# Main-v2_0.net
KiCad netlist of a schematic drawn in EAGLE
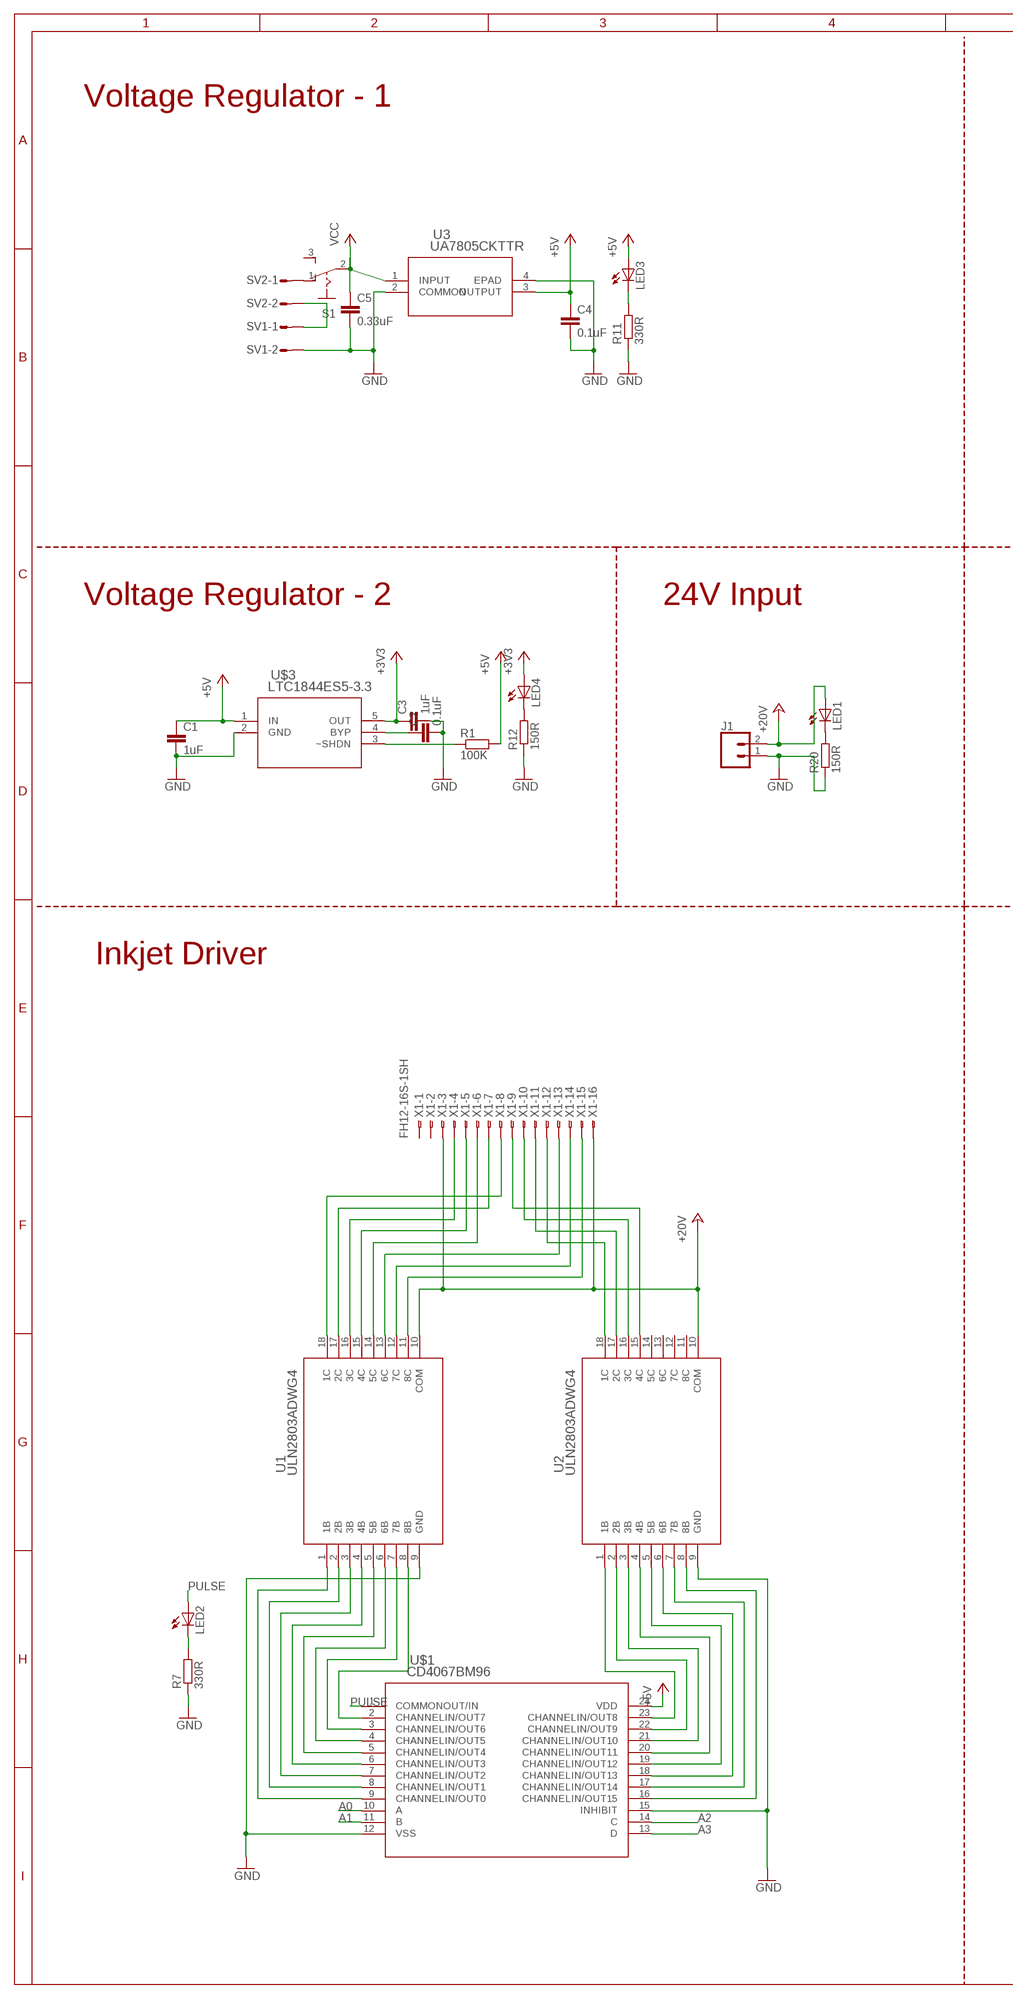
[diagram p0: schematic, sheet 1, part 1 of 2]
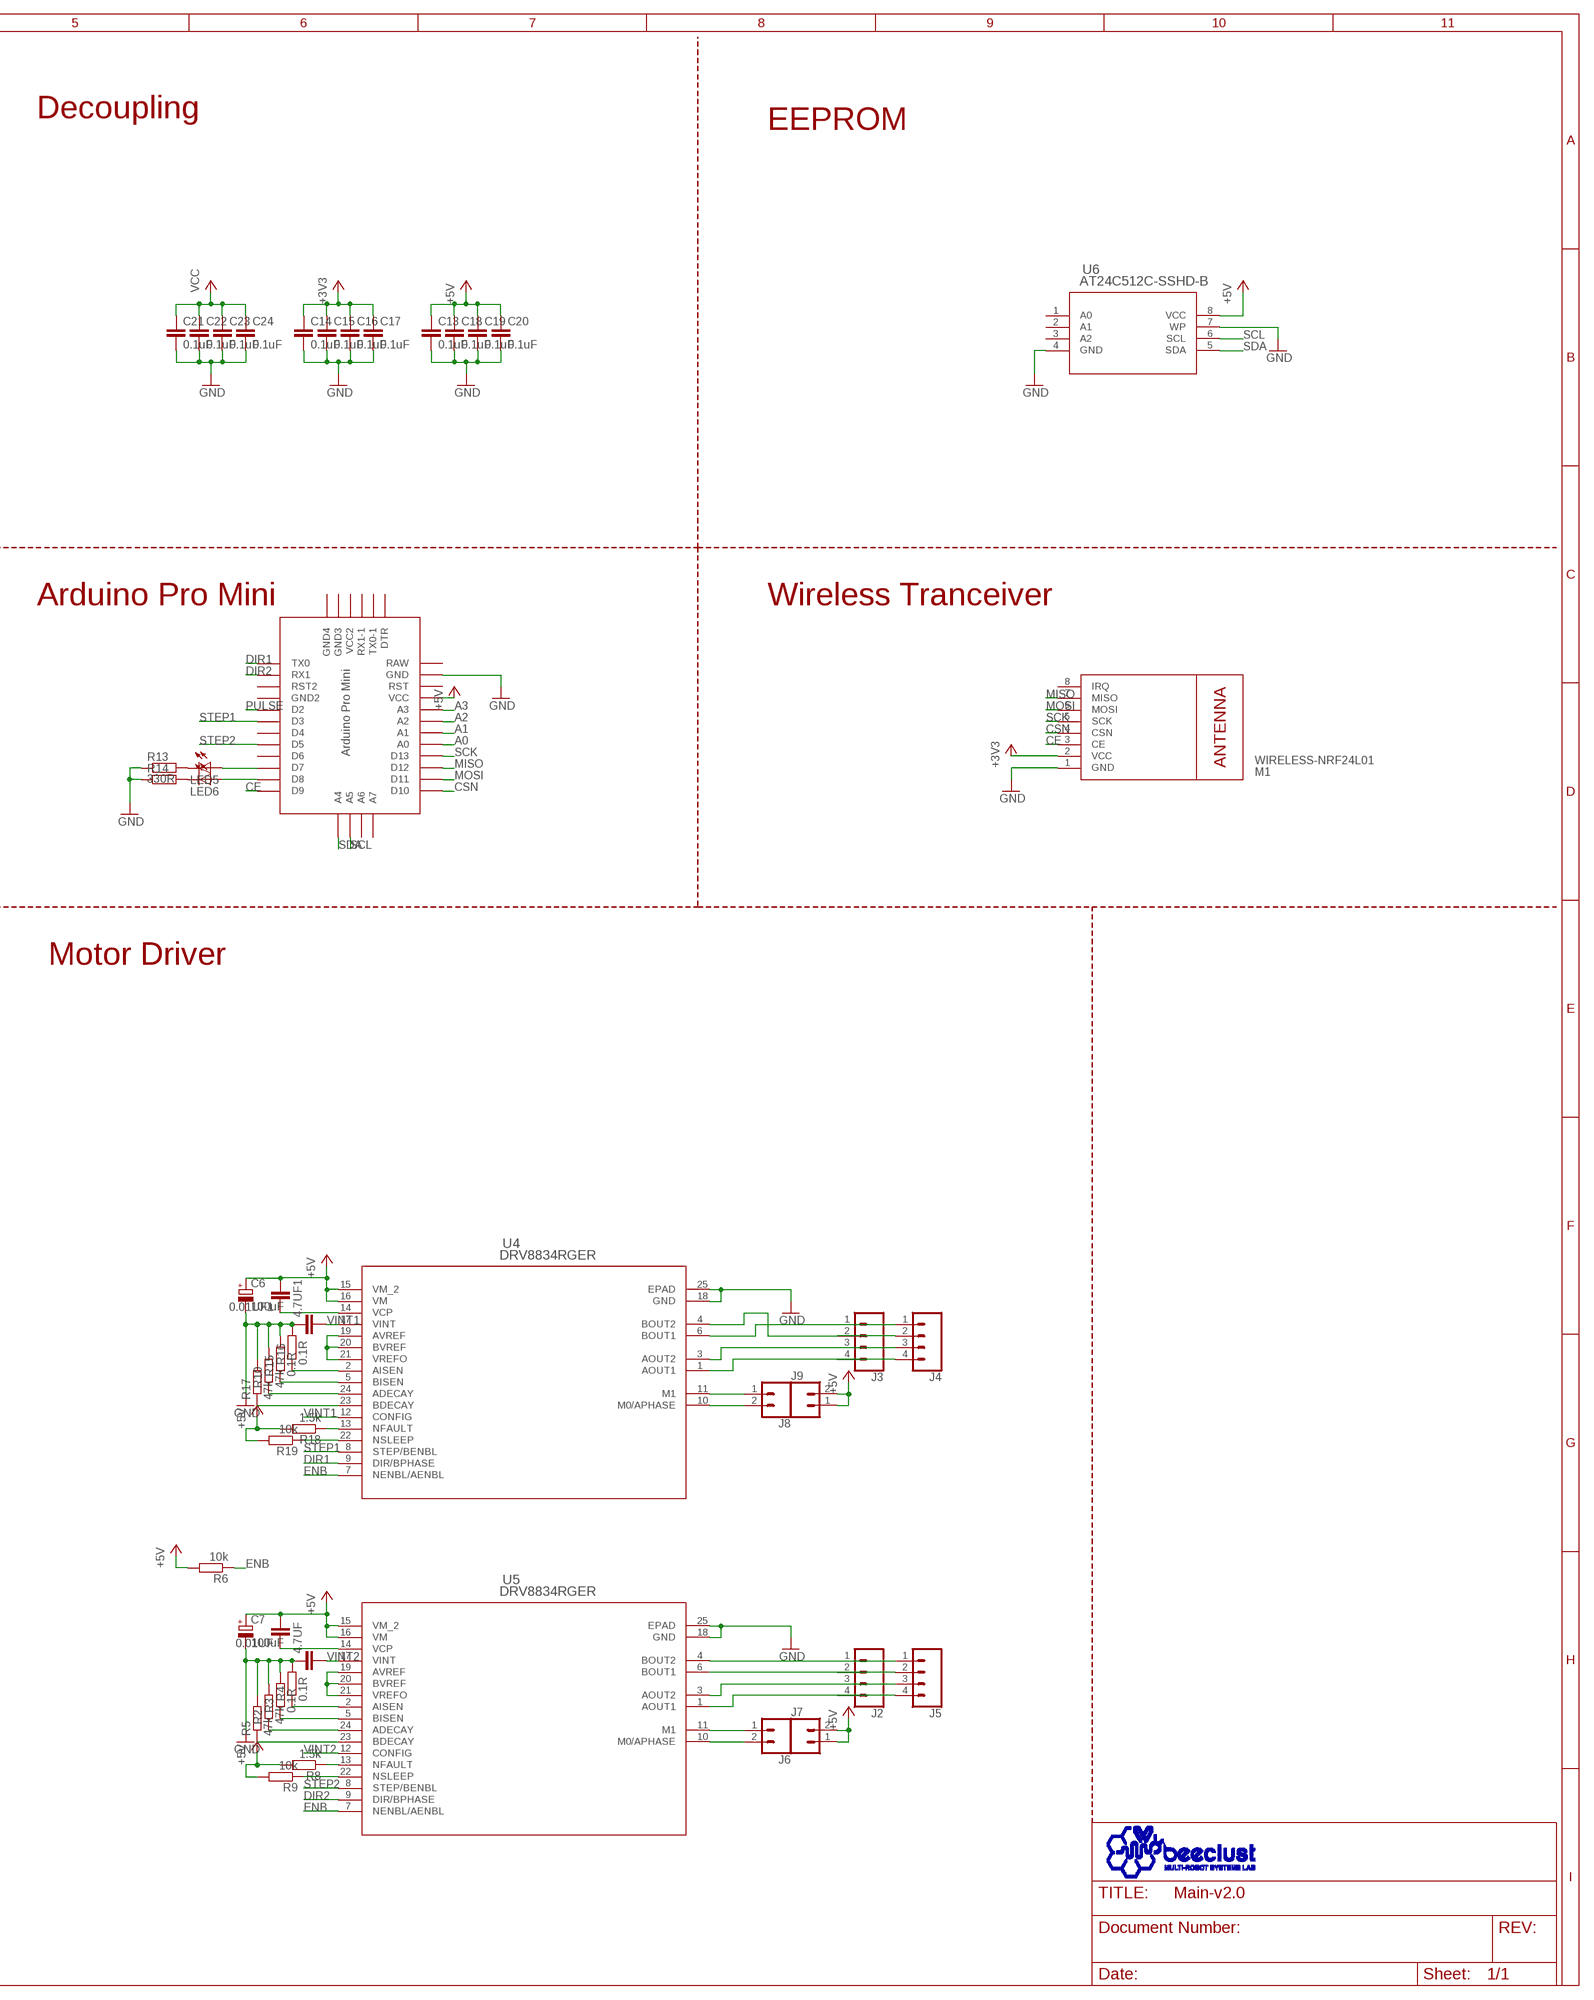
[diagram p1: schematic, sheet 1, part 2 of 2]

(export (version "E")
  (design (tool "Eeschema 10.0.6"))
  (components
    (comp (ref "0.01UF")
      (value "C-EUC0603K")
      (footprint "eagle-import:C0603K")
      (libsource (lib "eagle-import") (part "resistor_348_C-EUC0603K"))
    )
    (comp (ref "0.01UF1")
      (value "C-EUC0603K")
      (footprint "eagle-import:C0603K")
      (libsource (lib "eagle-import") (part "resistor_348_C-EUC0603K"))
    )
    (comp (ref "4.7UF")
      (value "C-EUC0603K")
      (footprint "eagle-import:C0603K")
      (libsource (lib "eagle-import") (part "resistor_348_C-EUC0603K"))
    )
    (comp (ref "4.7UF1")
      (value "C-EUC0603K")
      (footprint "eagle-import:C0603K")
      (libsource (lib "eagle-import") (part "resistor_348_C-EUC0603K"))
    )
    (comp (ref "C1")
      (value "1uF")
      (footprint "eagle-import:C0603")
      (libsource (lib "eagle-import") (part "C-EUC0603"))
    )
    (comp (ref "C2")
      (value "0.1uF")
      (footprint "eagle-import:C0603")
      (libsource (lib "eagle-import") (part "C-EUC0603"))
    )
    (comp (ref "C3")
      (value "1uF")
      (footprint "eagle-import:C0603")
      (libsource (lib "eagle-import") (part "C-EUC0603"))
    )
    (comp (ref "C4")
      (value "0.1uF")
      (footprint "eagle-import:C0603")
      (libsource (lib "eagle-import") (part "C-EUC0603"))
    )
    (comp (ref "C5")
      (value "0.33uF")
      (footprint "eagle-import:C0603")
      (libsource (lib "eagle-import") (part "C-EUC0603"))
    )
    (comp (ref "C6")
      (value "100uF")
      (footprint "eagle-import:E5-5")
      (libsource (lib "eagle-import") (part "CPOL-EUE5-5"))
    )
    (comp (ref "C7")
      (value "100uF")
      (footprint "eagle-import:E5-5")
      (libsource (lib "eagle-import") (part "CPOL-EUE5-5"))
    )
    (comp (ref "C13")
      (value "0.1uF")
      (footprint "eagle-import:C0603")
      (libsource (lib "eagle-import") (part "C-EUC0603"))
    )
    (comp (ref "C14")
      (value "0.1uF")
      (footprint "eagle-import:C0603")
      (libsource (lib "eagle-import") (part "C-EUC0603"))
    )
    (comp (ref "C15")
      (value "0.1uF")
      (footprint "eagle-import:C0603")
      (libsource (lib "eagle-import") (part "C-EUC0603"))
    )
    (comp (ref "C16")
      (value "0.1uF")
      (footprint "eagle-import:C0603")
      (libsource (lib "eagle-import") (part "C-EUC0603"))
    )
    (comp (ref "C17")
      (value "0.1uF")
      (footprint "eagle-import:C0603")
      (libsource (lib "eagle-import") (part "C-EUC0603"))
    )
    (comp (ref "C18")
      (value "0.1uF")
      (footprint "eagle-import:C0603")
      (libsource (lib "eagle-import") (part "C-EUC0603"))
    )
    (comp (ref "C19")
      (value "0.1uF")
      (footprint "eagle-import:C0603")
      (libsource (lib "eagle-import") (part "C-EUC0603"))
    )
    (comp (ref "C20")
      (value "0.1uF")
      (footprint "eagle-import:C0603")
      (libsource (lib "eagle-import") (part "C-EUC0603"))
    )
    (comp (ref "C21")
      (value "0.1uF")
      (footprint "eagle-import:C0603")
      (libsource (lib "eagle-import") (part "C-EUC0603"))
    )
    (comp (ref "C22")
      (value "0.1uF")
      (footprint "eagle-import:C0603")
      (libsource (lib "eagle-import") (part "C-EUC0603"))
    )
    (comp (ref "C23")
      (value "0.1uF")
      (footprint "eagle-import:C0603")
      (libsource (lib "eagle-import") (part "C-EUC0603"))
    )
    (comp (ref "C24")
      (value "0.1uF")
      (footprint "eagle-import:C0603")
      (libsource (lib "eagle-import") (part "C-EUC0603"))
    )
    (comp (ref "J1")
      (value "CONN_02")
      (footprint "eagle-import:1X02")
      (libsource (lib "eagle-import") (part "CONN_02"))
    )
    (comp (ref "J2")
      (value "CONN_04")
      (footprint "eagle-import:1X04")
      (libsource (lib "eagle-import") (part "CONN_04"))
    )
    (comp (ref "J3")
      (value "CONN_04")
      (footprint "eagle-import:1X04")
      (libsource (lib "eagle-import") (part "CONN_04"))
    )
    (comp (ref "J4")
      (value "CONN_04")
      (footprint "eagle-import:1X04")
      (libsource (lib "eagle-import") (part "CONN_04"))
    )
    (comp (ref "J5")
      (value "CONN_04")
      (footprint "eagle-import:1X04")
      (libsource (lib "eagle-import") (part "CONN_04"))
    )
    (comp (ref "J6")
      (value "CONN_02")
      (footprint "eagle-import:1X02")
      (libsource (lib "eagle-import") (part "CONN_02"))
    )
    (comp (ref "J7")
      (value "CONN_02")
      (footprint "eagle-import:1X02")
      (libsource (lib "eagle-import") (part "CONN_02"))
    )
    (comp (ref "J8")
      (value "CONN_02")
      (footprint "eagle-import:1X02")
      (libsource (lib "eagle-import") (part "CONN_02"))
    )
    (comp (ref "J9")
      (value "CONN_02")
      (footprint "eagle-import:1X02")
      (libsource (lib "eagle-import") (part "CONN_02"))
    )
    (comp (ref "LED1")
      (value "LEDSML0603")
      (footprint "eagle-import:SML0603")
      (libsource (lib "eagle-import") (part "LEDSML0603"))
    )
    (comp (ref "LED2")
      (value "LEDSML0603")
      (footprint "eagle-import:SML0603")
      (libsource (lib "eagle-import") (part "LEDSML0603"))
    )
    (comp (ref "LED3")
      (value "LEDSML0603")
      (footprint "eagle-import:SML0603")
      (libsource (lib "eagle-import") (part "LEDSML0603"))
    )
    (comp (ref "LED4")
      (value "LEDSML0603")
      (footprint "eagle-import:SML0603")
      (libsource (lib "eagle-import") (part "LEDSML0603"))
    )
    (comp (ref "LED5")
      (value "LEDSML0603")
      (footprint "eagle-import:SML0603")
      (libsource (lib "eagle-import") (part "LEDSML0603"))
    )
    (comp (ref "LED6")
      (value "LEDSML0603")
      (footprint "eagle-import:SML0603")
      (libsource (lib "eagle-import") (part "LEDSML0603"))
    )
    (comp (ref "M1")
      (value "WIRELESS-NRF24L01")
      (footprint "eagle-import:WIRELESS-NRF24L01")
      (libsource (lib "eagle-import") (part "WIRELESS-NRF24L01"))
    )
    (comp (ref "R1")
      (value "100K")
      (footprint "eagle-import:R0603")
      (libsource (lib "eagle-import") (part "R-EU_R0603"))
    )
    (comp (ref "R2")
      (value "47k")
      (footprint "eagle-import:R0402")
      (libsource (lib "eagle-import") (part "resistor_348_R-EU_R0402"))
    )
    (comp (ref "R3")
      (value "0.1R")
      (footprint "eagle-import:R0402")
      (libsource (lib "eagle-import") (part "resistor_348_R-EU_R0402"))
    )
    (comp (ref "R4")
      (value "0.1R")
      (footprint "eagle-import:R0402")
      (libsource (lib "eagle-import") (part "resistor_348_R-EU_R0402"))
    )
    (comp (ref "R5")
      (value "47k")
      (footprint "eagle-import:R0402")
      (libsource (lib "eagle-import") (part "resistor_348_R-EU_R0402"))
    )
    (comp (ref "R6")
      (value "10k")
      (footprint "eagle-import:R0402")
      (libsource (lib "eagle-import") (part "resistor_348_R-EU_R0402"))
    )
    (comp (ref "R7")
      (value "330R")
      (footprint "eagle-import:R0603")
      (libsource (lib "eagle-import") (part "R-EU_R0603"))
    )
    (comp (ref "R8")
      (value "1.5k")
      (footprint "eagle-import:R0402")
      (libsource (lib "eagle-import") (part "resistor_348_R-EU_R0402"))
    )
    (comp (ref "R9")
      (value "10k")
      (footprint "eagle-import:R0402")
      (libsource (lib "eagle-import") (part "resistor_348_R-EU_R0402"))
    )
    (comp (ref "R10")
      (value "47k")
      (footprint "eagle-import:R0402")
      (libsource (lib "eagle-import") (part "resistor_348_R-EU_R0402"))
    )
    (comp (ref "R11")
      (value "330R")
      (footprint "eagle-import:R0603")
      (libsource (lib "eagle-import") (part "R-EU_R0603"))
    )
    (comp (ref "R12")
      (value "150R")
      (footprint "eagle-import:R0603")
      (libsource (lib "eagle-import") (part "R-EU_R0603"))
    )
    (comp (ref "R13")
      (value "330R")
      (footprint "eagle-import:R0603")
      (libsource (lib "eagle-import") (part "R-EU_R0603"))
    )
    (comp (ref "R14")
      (value "R-EU_R0603")
      (footprint "eagle-import:R0603")
      (libsource (lib "eagle-import") (part "R-EU_R0603"))
    )
    (comp (ref "R15")
      (value "0.1R")
      (footprint "eagle-import:R0402")
      (libsource (lib "eagle-import") (part "resistor_348_R-EU_R0402"))
    )
    (comp (ref "R16")
      (value "0.1R")
      (footprint "eagle-import:R0402")
      (libsource (lib "eagle-import") (part "resistor_348_R-EU_R0402"))
    )
    (comp (ref "R17")
      (value "47k")
      (footprint "eagle-import:R0402")
      (libsource (lib "eagle-import") (part "resistor_348_R-EU_R0402"))
    )
    (comp (ref "R18")
      (value "1.5k")
      (footprint "eagle-import:R0402")
      (libsource (lib "eagle-import") (part "resistor_348_R-EU_R0402"))
    )
    (comp (ref "R19")
      (value "10k")
      (footprint "eagle-import:R0402")
      (libsource (lib "eagle-import") (part "resistor_348_R-EU_R0402"))
    )
    (comp (ref "R20")
      (value "150R")
      (footprint "eagle-import:R0603")
      (libsource (lib "eagle-import") (part "R-EU_R0603"))
    )
    (comp (ref "S1")
      (value "255SB")
      (footprint "eagle-import:255SB")
      (libsource (lib "eagle-import") (part "255SB"))
    )
    (comp (ref "SV1")
      (value "L02P")
      (footprint "eagle-import:L02P")
      (libsource (lib "eagle-import") (part "L02P"))
    )
    (comp (ref "SV2")
      (value "L02P")
      (footprint "eagle-import:L02P")
      (libsource (lib "eagle-import") (part "L02P"))
    )
    (comp (ref "U$1")
      (value "CD4067BM96")
      (footprint "eagle-import:DW24")
      (fields (field (name "MANUFACTURER_PART_NUMBER") "CD4067B_DW_24"))
      (libsource (lib "eagle-import") (part "CD4067BM96"))
    )
    (comp (ref "U$2")
      (value "PRO-MINI")
      (footprint "eagle-import:PRO-MINI")
      (libsource (lib "eagle-import") (part "PRO-MINI"))
    )
    (comp (ref "U$3")
      (value "LTC1844ES5-3.3")
      (footprint "eagle-import:TSOT-23_S5")
      (libsource (lib "eagle-import") (part "LTC1844ES5-3.3"))
    )
    (comp (ref "U$5")
      (value "BEECLUST-LOGO")
      (footprint "eagle-import:LOGO")
      (libsource (lib "eagle-import") (part "BEECLUST-LOGO"))
    )
    (comp (ref "U1")
      (value "ULN2803ADWG4")
      (footprint "eagle-import:DW18")
      (libsource (lib "eagle-import") (part "ULN2803ADWG4"))
    )
    (comp (ref "U2")
      (value "ULN2803ADWG4")
      (footprint "eagle-import:DW18")
      (libsource (lib "eagle-import") (part "ULN2803ADWG4"))
    )
    (comp (ref "U3")
      (value "UA7805CKTTR")
      (footprint "eagle-import:KTT3_6P22X6P6")
      (libsource (lib "eagle-import") (part "UA7805CKTTR"))
    )
    (comp (ref "U4")
      (value "DRV8834RGER")
      (footprint "eagle-import:RGE24_2P45X2P45")
      (libsource (lib "eagle-import") (part "DRV8834RGER"))
    )
    (comp (ref "U5")
      (value "DRV8834RGER")
      (footprint "eagle-import:RGE24_2P45X2P45")
      (libsource (lib "eagle-import") (part "DRV8834RGER"))
    )
    (comp (ref "U6")
      (value "AT24C512C-SSHD-B")
      (footprint "eagle-import:8S1")
      (fields (field (name "MANUFACTURER_PART_NUMBER") "AT24C512CSSHDB"))
      (libsource (lib "eagle-import") (part "AT24C512C-SSHD-B"))
    )
    (comp (ref "X1")
      (value "FH12-16S-1SH")
      (footprint "eagle-import:FH12-16S-1SH")
      (libsource (lib "eagle-import") (part "FH12-16S-1SH"))
    )
  )
  (nets
    (net (code "1") (name "+3V3") (class "Default")
      (node (ref "C14") (pin "1") (pinfunction "1_1") (pintype "passive"))
      (node (ref "C15") (pin "1") (pinfunction "1_1") (pintype "passive"))
      (node (ref "C16") (pin "1") (pinfunction "1_1") (pintype "passive"))
      (node (ref "C17") (pin "1") (pinfunction "1_1") (pintype "passive"))
      (node (ref "C3") (pin "1") (pinfunction "1_1") (pintype "passive"))
      (node (ref "LED4") (pin "A") (pinfunction "A_A") (pintype "passive"))
      (node (ref "M1") (pin "2") (pinfunction "VCC_2") (pintype "power_in"))
      (node (ref "U$3") (pin "5") (pinfunction "OUT_5") (pintype "passive"))
    )
    (net (code "2") (name "+5V") (class "Default")
      (node (ref "0.01UF") (pin "2") (pinfunction "2_2") (pintype "passive"))
      (node (ref "0.01UF1") (pin "2") (pinfunction "2_2") (pintype "passive"))
      (node (ref "C1") (pin "1") (pinfunction "1_1") (pintype "passive"))
      (node (ref "C13") (pin "1") (pinfunction "1_1") (pintype "passive"))
      (node (ref "C18") (pin "1") (pinfunction "1_1") (pintype "passive"))
      (node (ref "C19") (pin "1") (pinfunction "1_1") (pintype "passive"))
      (node (ref "C20") (pin "1") (pinfunction "1_1") (pintype "passive"))
      (node (ref "C4") (pin "1") (pinfunction "1_1") (pintype "passive"))
      (node (ref "C6") (pin "+") (pinfunction "+_+") (pintype "passive"))
      (node (ref "C7") (pin "+") (pinfunction "+_+") (pintype "passive"))
      (node (ref "J7") (pin "1") (pinfunction "1_1") (pintype "passive"))
      (node (ref "J7") (pin "2") (pinfunction "2_2") (pintype "passive"))
      (node (ref "J9") (pin "1") (pinfunction "1_1") (pintype "passive"))
      (node (ref "J9") (pin "2") (pinfunction "2_2") (pintype "passive"))
      (node (ref "LED3") (pin "A") (pinfunction "A_A") (pintype "passive"))
      (node (ref "R1") (pin "2") (pinfunction "2_2") (pintype "passive"))
      (node (ref "R18") (pin "2") (pinfunction "2_2") (pintype "passive"))
      (node (ref "R19") (pin "2") (pinfunction "2_2") (pintype "passive"))
      (node (ref "R6") (pin "2") (pinfunction "2_2") (pintype "passive"))
      (node (ref "R8") (pin "2") (pinfunction "2_2") (pintype "passive"))
      (node (ref "R9") (pin "2") (pinfunction "2_2") (pintype "passive"))
      (node (ref "U$1") (pin "24") (pinfunction "VDD_24") (pintype "power_in"))
      (node (ref "U$2") (pin "VCC") (pinfunction "VCC_VCC") (pintype "bidirectional"))
      (node (ref "U$3") (pin "1") (pinfunction "IN_1") (pintype "passive"))
      (node (ref "U3") (pin "3") (pinfunction "OUTPUT_3") (pintype "output"))
      (node (ref "U4") (pin "15") (pinfunction "VM_2_15") (pintype "power_in"))
      (node (ref "U4") (pin "16") (pinfunction "VM_16") (pintype "power_in"))
      (node (ref "U5") (pin "15") (pinfunction "VM_2_15") (pintype "power_in"))
      (node (ref "U5") (pin "16") (pinfunction "VM_16") (pintype "power_in"))
      (node (ref "U6") (pin "8") (pinfunction "VCC_8") (pintype "power_in"))
    )
    (net (code "3") (name "+20V") (class "Default")
      (node (ref "J1") (pin "2") (pinfunction "2_2") (pintype "passive"))
      (node (ref "LED1") (pin "A") (pinfunction "A_A") (pintype "passive"))
      (node (ref "U1") (pin "10") (pinfunction "COM_10") (pintype "passive"))
      (node (ref "U2") (pin "10") (pinfunction "COM_10") (pintype "passive"))
      (node (ref "X1") (pin "16") (pinfunction "1_16") (pintype "passive"))
      (node (ref "X1") (pin "3") (pinfunction "1_3") (pintype "passive"))
    )
    (net (code "4") (name "/A0") (class "Default")
      (node (ref "U$1") (pin "10") (pinfunction "A_10") (pintype "passive"))
      (node (ref "U$2") (pin "A0") (pinfunction "A0_A0") (pintype "bidirectional"))
    )
    (net (code "5") (name "/A1") (class "Default")
      (node (ref "U$1") (pin "11") (pinfunction "B_11") (pintype "passive"))
      (node (ref "U$2") (pin "A1") (pinfunction "A1_A1") (pintype "bidirectional"))
    )
    (net (code "6") (name "/A2") (class "Default")
      (node (ref "U$1") (pin "14") (pinfunction "C_14") (pintype "passive"))
      (node (ref "U$2") (pin "A2") (pinfunction "A2_A2") (pintype "bidirectional"))
    )
    (net (code "7") (name "/A3") (class "Default")
      (node (ref "U$1") (pin "13") (pinfunction "D_13") (pintype "passive"))
      (node (ref "U$2") (pin "A3") (pinfunction "A3_A3") (pintype "bidirectional"))
    )
    (net (code "8") (name "/CE") (class "Default")
      (node (ref "M1") (pin "3") (pinfunction "CE_3") (pintype "bidirectional"))
      (node (ref "U$2") (pin "D9") (pinfunction "D9_D9") (pintype "bidirectional"))
    )
    (net (code "9") (name "/CSN") (class "Default")
      (node (ref "M1") (pin "4") (pinfunction "CSN_4") (pintype "bidirectional"))
      (node (ref "U$2") (pin "D10") (pinfunction "D10_D10") (pintype "bidirectional"))
    )
    (net (code "10") (name "/DIR1") (class "Default")
      (node (ref "U$2") (pin "TX0") (pinfunction "TX0_TX0") (pintype "bidirectional"))
      (node (ref "U4") (pin "9") (pinfunction "DIR/BPHASE_9") (pintype "input"))
    )
    (net (code "11") (name "/DIR2") (class "Default")
      (node (ref "U$2") (pin "RX1") (pinfunction "RX1_RX1") (pintype "bidirectional"))
      (node (ref "U5") (pin "9") (pinfunction "DIR/BPHASE_9") (pintype "input"))
    )
    (net (code "12") (name "/ENB") (class "Default")
      (node (ref "R6") (pin "1") (pinfunction "1_1") (pintype "passive"))
      (node (ref "U4") (pin "7") (pinfunction "NENBL/AENBL_7") (pintype "input"))
      (node (ref "U5") (pin "7") (pinfunction "NENBL/AENBL_7") (pintype "input"))
    )
    (net (code "13") (name "/MISO") (class "Default")
      (node (ref "M1") (pin "7") (pinfunction "MISO_7") (pintype "bidirectional"))
      (node (ref "U$2") (pin "D12") (pinfunction "D12_D12") (pintype "bidirectional"))
    )
    (net (code "14") (name "/MOSI") (class "Default")
      (node (ref "M1") (pin "6") (pinfunction "MOSI_6") (pintype "bidirectional"))
      (node (ref "U$2") (pin "D11") (pinfunction "D11_D11") (pintype "bidirectional"))
    )
    (net (code "15") (name "/PULSE") (class "Default")
      (node (ref "LED2") (pin "A") (pinfunction "A_A") (pintype "passive"))
      (node (ref "U$1") (pin "1") (pinfunction "COMMONOUT/IN_1") (pintype "bidirectional"))
      (node (ref "U$2") (pin "D2") (pinfunction "D2_D2") (pintype "bidirectional"))
    )
    (net (code "16") (name "/RAW") (class "Default")
      (node (ref "U$2") (pin "RAW") (pinfunction "RAW_RAW") (pintype "power_in"))
    )
    (net (code "17") (name "/SCK") (class "Default")
      (node (ref "M1") (pin "5") (pinfunction "SCK_5") (pintype "bidirectional"))
      (node (ref "U$2") (pin "D13") (pinfunction "D13_D13") (pintype "bidirectional"))
    )
    (net (code "18") (name "/SCL") (class "Default")
      (node (ref "U$2") (pin "A5") (pinfunction "A5_A5") (pintype "bidirectional"))
      (node (ref "U6") (pin "6") (pinfunction "SCL_6") (pintype "input"))
    )
    (net (code "19") (name "/SDA") (class "Default")
      (node (ref "U$2") (pin "A4") (pinfunction "A4_A4") (pintype "bidirectional"))
      (node (ref "U6") (pin "5") (pinfunction "SDA_5") (pintype "passive"))
    )
    (net (code "20") (name "/STEP1") (class "Default")
      (node (ref "U$2") (pin "D3") (pinfunction "D3_D3") (pintype "bidirectional"))
      (node (ref "U4") (pin "8") (pinfunction "STEP/BENBL_8") (pintype "input"))
    )
    (net (code "21") (name "/STEP2") (class "Default")
      (node (ref "U$2") (pin "D5") (pinfunction "D5_D5") (pintype "bidirectional"))
      (node (ref "U5") (pin "8") (pinfunction "STEP/BENBL_8") (pintype "input"))
    )
    (net (code "22") (name "/VINT1") (class "Default")
      (node (ref "4.7UF1") (pin "2") (pinfunction "2_2") (pintype "passive"))
      (node (ref "U4") (pin "12") (pinfunction "CONFIG_12") (pintype "input"))
      (node (ref "U4") (pin "17") (pinfunction "VINT_17") (pintype "passive"))
    )
    (net (code "23") (name "/VINT2") (class "Default")
      (node (ref "4.7UF") (pin "2") (pinfunction "2_2") (pintype "passive"))
      (node (ref "U5") (pin "12") (pinfunction "CONFIG_12") (pintype "input"))
      (node (ref "U5") (pin "17") (pinfunction "VINT_17") (pintype "passive"))
    )
    (net (code "24") (name "GND") (class "Default")
      (node (ref "4.7UF") (pin "1") (pinfunction "1_1") (pintype "passive"))
      (node (ref "4.7UF1") (pin "1") (pinfunction "1_1") (pintype "passive"))
      (node (ref "C1") (pin "2") (pinfunction "2_2") (pintype "passive"))
      (node (ref "C13") (pin "2") (pinfunction "2_2") (pintype "passive"))
      (node (ref "C14") (pin "2") (pinfunction "2_2") (pintype "passive"))
      (node (ref "C15") (pin "2") (pinfunction "2_2") (pintype "passive"))
      (node (ref "C16") (pin "2") (pinfunction "2_2") (pintype "passive"))
      (node (ref "C17") (pin "2") (pinfunction "2_2") (pintype "passive"))
      (node (ref "C18") (pin "2") (pinfunction "2_2") (pintype "passive"))
      (node (ref "C19") (pin "2") (pinfunction "2_2") (pintype "passive"))
      (node (ref "C2") (pin "2") (pinfunction "2_2") (pintype "passive"))
      (node (ref "C20") (pin "2") (pinfunction "2_2") (pintype "passive"))
      (node (ref "C21") (pin "2") (pinfunction "2_2") (pintype "passive"))
      (node (ref "C22") (pin "2") (pinfunction "2_2") (pintype "passive"))
      (node (ref "C23") (pin "2") (pinfunction "2_2") (pintype "passive"))
      (node (ref "C24") (pin "2") (pinfunction "2_2") (pintype "passive"))
      (node (ref "C3") (pin "2") (pinfunction "2_2") (pintype "passive"))
      (node (ref "C4") (pin "2") (pinfunction "2_2") (pintype "passive"))
      (node (ref "C5") (pin "2") (pinfunction "2_2") (pintype "passive"))
      (node (ref "C6") (pin "-") (pinfunction "-_-") (pintype "passive"))
      (node (ref "C7") (pin "-") (pinfunction "-_-") (pintype "passive"))
      (node (ref "J1") (pin "1") (pinfunction "1_1") (pintype "passive"))
      (node (ref "M1") (pin "1") (pinfunction "GND_1") (pintype "power_in"))
      (node (ref "R10") (pin "2") (pinfunction "2_2") (pintype "passive"))
      (node (ref "R11") (pin "1") (pinfunction "1_1") (pintype "passive"))
      (node (ref "R12") (pin "1") (pinfunction "1_1") (pintype "passive"))
      (node (ref "R13") (pin "1") (pinfunction "1_1") (pintype "passive"))
      (node (ref "R14") (pin "1") (pinfunction "1_1") (pintype "passive"))
      (node (ref "R15") (pin "2") (pinfunction "2_2") (pintype "passive"))
      (node (ref "R16") (pin "2") (pinfunction "2_2") (pintype "passive"))
      (node (ref "R17") (pin "2") (pinfunction "2_2") (pintype "passive"))
      (node (ref "R2") (pin "2") (pinfunction "2_2") (pintype "passive"))
      (node (ref "R20") (pin "1") (pinfunction "1_1") (pintype "passive"))
      (node (ref "R3") (pin "2") (pinfunction "2_2") (pintype "passive"))
      (node (ref "R4") (pin "2") (pinfunction "2_2") (pintype "passive"))
      (node (ref "R5") (pin "2") (pinfunction "2_2") (pintype "passive"))
      (node (ref "R7") (pin "1") (pinfunction "1_1") (pintype "passive"))
      (node (ref "SV1") (pin "2") (pinfunction "S_2") (pintype "passive"))
      (node (ref "U$1") (pin "12") (pinfunction "VSS_12") (pintype "power_in"))
      (node (ref "U$1") (pin "15") (pinfunction "INHIBIT_15") (pintype "passive"))
      (node (ref "U$2") (pin "GND") (pinfunction "GND_GND") (pintype "input"))
      (node (ref "U$3") (pin "2") (pinfunction "GND_2") (pintype "passive"))
      (node (ref "U1") (pin "9") (pinfunction "GND_9") (pintype "passive"))
      (node (ref "U2") (pin "9") (pinfunction "GND_9") (pintype "passive"))
      (node (ref "U3") (pin "2") (pinfunction "COMMON_2") (pintype "power_in"))
      (node (ref "U3") (pin "4") (pinfunction "EPAD_4") (pintype "passive"))
      (node (ref "U4") (pin "18") (pinfunction "GND_18") (pintype "power_in"))
      (node (ref "U4") (pin "25") (pinfunction "EPAD_25") (pintype "passive"))
      (node (ref "U5") (pin "18") (pinfunction "GND_18") (pintype "power_in"))
      (node (ref "U5") (pin "25") (pinfunction "EPAD_25") (pintype "passive"))
      (node (ref "U6") (pin "4") (pinfunction "GND_4") (pintype "power_in"))
      (node (ref "U6") (pin "7") (pinfunction "WP_7") (pintype "passive"))
    )
    (net (code "25") (name "Net-(LED1-PadC)") (class "Default")
      (node (ref "LED1") (pin "C") (pinfunction "C_C") (pintype "passive"))
      (node (ref "R20") (pin "2") (pinfunction "2_2") (pintype "passive"))
    )
    (net (code "26") (name "Net-(LED2-PadC)") (class "Default")
      (node (ref "LED2") (pin "C") (pinfunction "C_C") (pintype "passive"))
      (node (ref "R7") (pin "2") (pinfunction "2_2") (pintype "passive"))
    )
    (net (code "27") (name "Net-(LED3-PadC)") (class "Default")
      (node (ref "LED3") (pin "C") (pinfunction "C_C") (pintype "passive"))
      (node (ref "R11") (pin "2") (pinfunction "2_2") (pintype "passive"))
    )
    (net (code "28") (name "Net-(LED4-PadC)") (class "Default")
      (node (ref "LED4") (pin "C") (pinfunction "C_C") (pintype "passive"))
      (node (ref "R12") (pin "2") (pinfunction "2_2") (pintype "passive"))
    )
    (net (code "29") (name "Net-(LED5-PadA)") (class "Default")
      (node (ref "LED5") (pin "A") (pinfunction "A_A") (pintype "passive"))
      (node (ref "U$2") (pin "D7") (pinfunction "D7_D7") (pintype "bidirectional"))
    )
    (net (code "30") (name "Net-(LED5-PadC)") (class "Default")
      (node (ref "LED5") (pin "C") (pinfunction "C_C") (pintype "passive"))
      (node (ref "R13") (pin "2") (pinfunction "2_2") (pintype "passive"))
    )
    (net (code "31") (name "Net-(LED6-PadA)") (class "Default")
      (node (ref "LED6") (pin "A") (pinfunction "A_A") (pintype "passive"))
      (node (ref "U$2") (pin "D8") (pinfunction "D8_D8") (pintype "bidirectional"))
    )
    (net (code "32") (name "Net-(LED6-PadC)") (class "Default")
      (node (ref "LED6") (pin "C") (pinfunction "C_C") (pintype "passive"))
      (node (ref "R14") (pin "2") (pinfunction "2_2") (pintype "passive"))
    )
    (net (code "33") (name "Net-(S1-O)") (class "Default")
      (node (ref "S1") (pin "1") (pinfunction "O_1") (pintype "passive"))
      (node (ref "SV2") (pin "1") (pinfunction "S_1") (pintype "passive"))
    )
    (net (code "34") (name "Net-(SV1A-S)") (class "Default")
      (node (ref "SV1") (pin "1") (pinfunction "S_1") (pintype "passive"))
      (node (ref "SV2") (pin "2") (pinfunction "S_2") (pintype "passive"))
    )
    (net (code "35") (name "Net-(U$1-CHANNELIN{slash}OUT0)") (class "Default")
      (node (ref "U$1") (pin "9") (pinfunction "CHANNELIN/OUT0_9") (pintype "bidirectional"))
      (node (ref "U1") (pin "1") (pinfunction "1B_1") (pintype "passive"))
    )
    (net (code "36") (name "Net-(U$1-CHANNELIN{slash}OUT1)") (class "Default")
      (node (ref "U$1") (pin "8") (pinfunction "CHANNELIN/OUT1_8") (pintype "bidirectional"))
      (node (ref "U1") (pin "2") (pinfunction "2B_2") (pintype "passive"))
    )
    (net (code "37") (name "Net-(U$1-CHANNELIN{slash}OUT2)") (class "Default")
      (node (ref "U$1") (pin "7") (pinfunction "CHANNELIN/OUT2_7") (pintype "bidirectional"))
      (node (ref "U1") (pin "3") (pinfunction "3B_3") (pintype "passive"))
    )
    (net (code "38") (name "Net-(U$1-CHANNELIN{slash}OUT3)") (class "Default")
      (node (ref "U$1") (pin "6") (pinfunction "CHANNELIN/OUT3_6") (pintype "bidirectional"))
      (node (ref "U1") (pin "4") (pinfunction "4B_4") (pintype "passive"))
    )
    (net (code "39") (name "Net-(U$1-CHANNELIN{slash}OUT4)") (class "Default")
      (node (ref "U$1") (pin "5") (pinfunction "CHANNELIN/OUT4_5") (pintype "bidirectional"))
      (node (ref "U1") (pin "5") (pinfunction "5B_5") (pintype "passive"))
    )
    (net (code "40") (name "Net-(U$1-CHANNELIN{slash}OUT5)") (class "Default")
      (node (ref "U$1") (pin "4") (pinfunction "CHANNELIN/OUT5_4") (pintype "bidirectional"))
      (node (ref "U1") (pin "6") (pinfunction "6B_6") (pintype "passive"))
    )
    (net (code "41") (name "Net-(U$1-CHANNELIN{slash}OUT6)") (class "Default")
      (node (ref "U$1") (pin "3") (pinfunction "CHANNELIN/OUT6_3") (pintype "bidirectional"))
      (node (ref "U1") (pin "7") (pinfunction "7B_7") (pintype "passive"))
    )
    (net (code "42") (name "Net-(U$1-CHANNELIN{slash}OUT7)") (class "Default")
      (node (ref "U$1") (pin "2") (pinfunction "CHANNELIN/OUT7_2") (pintype "bidirectional"))
      (node (ref "U1") (pin "8") (pinfunction "8B_8") (pintype "passive"))
    )
    (net (code "43") (name "Net-(U$1-CHANNELIN{slash}OUT8)") (class "Default")
      (node (ref "U$1") (pin "23") (pinfunction "CHANNELIN/OUT8_23") (pintype "bidirectional"))
      (node (ref "U2") (pin "1") (pinfunction "1B_1") (pintype "passive"))
    )
    (net (code "44") (name "Net-(U$1-CHANNELIN{slash}OUT9)") (class "Default")
      (node (ref "U$1") (pin "22") (pinfunction "CHANNELIN/OUT9_22") (pintype "bidirectional"))
      (node (ref "U2") (pin "2") (pinfunction "2B_2") (pintype "passive"))
    )
    (net (code "45") (name "Net-(U$1-CHANNELIN{slash}OUT10)") (class "Default")
      (node (ref "U$1") (pin "21") (pinfunction "CHANNELIN/OUT10_21") (pintype "bidirectional"))
      (node (ref "U2") (pin "3") (pinfunction "3B_3") (pintype "passive"))
    )
    (net (code "46") (name "Net-(U$1-CHANNELIN{slash}OUT11)") (class "Default")
      (node (ref "U$1") (pin "20") (pinfunction "CHANNELIN/OUT11_20") (pintype "bidirectional"))
      (node (ref "U2") (pin "4") (pinfunction "4B_4") (pintype "passive"))
    )
    (net (code "47") (name "Net-(U$1-CHANNELIN{slash}OUT12)") (class "Default")
      (node (ref "U$1") (pin "19") (pinfunction "CHANNELIN/OUT12_19") (pintype "bidirectional"))
      (node (ref "U2") (pin "5") (pinfunction "5B_5") (pintype "passive"))
    )
    (net (code "48") (name "Net-(U$1-CHANNELIN{slash}OUT13)") (class "Default")
      (node (ref "U$1") (pin "18") (pinfunction "CHANNELIN/OUT13_18") (pintype "bidirectional"))
      (node (ref "U2") (pin "6") (pinfunction "6B_6") (pintype "passive"))
    )
    (net (code "49") (name "Net-(U$1-CHANNELIN{slash}OUT14)") (class "Default")
      (node (ref "U$1") (pin "17") (pinfunction "CHANNELIN/OUT14_17") (pintype "bidirectional"))
      (node (ref "U2") (pin "7") (pinfunction "7B_7") (pintype "passive"))
    )
    (net (code "50") (name "Net-(U$1-CHANNELIN{slash}OUT15)") (class "Default")
      (node (ref "U$1") (pin "16") (pinfunction "CHANNELIN/OUT15_16") (pintype "bidirectional"))
      (node (ref "U2") (pin "8") (pinfunction "8B_8") (pintype "passive"))
    )
    (net (code "51") (name "Net-(U$3-BYP)") (class "Default")
      (node (ref "C2") (pin "1") (pinfunction "1_1") (pintype "passive"))
      (node (ref "U$3") (pin "4") (pinfunction "BYP_4") (pintype "passive"))
    )
    (net (code "52") (name "Net-(U$3-~{SHDN})") (class "Default")
      (node (ref "R1") (pin "1") (pinfunction "1_1") (pintype "passive"))
      (node (ref "U$3") (pin "3") (pinfunction "~{SHDN}_3") (pintype "passive"))
    )
    (net (code "53") (name "Net-(U1-1C)") (class "Default")
      (node (ref "U1") (pin "18") (pinfunction "1C_18") (pintype "passive"))
      (node (ref "X1") (pin "8") (pinfunction "1_8") (pintype "passive"))
    )
    (net (code "54") (name "Net-(U1-2C)") (class "Default")
      (node (ref "U1") (pin "17") (pinfunction "2C_17") (pintype "passive"))
      (node (ref "X1") (pin "7") (pinfunction "1_7") (pintype "passive"))
    )
    (net (code "55") (name "Net-(U1-3C)") (class "Default")
      (node (ref "U1") (pin "16") (pinfunction "3C_16") (pintype "passive"))
      (node (ref "X1") (pin "4") (pinfunction "1_4") (pintype "passive"))
    )
    (net (code "56") (name "Net-(U1-4C)") (class "Default")
      (node (ref "U1") (pin "15") (pinfunction "4C_15") (pintype "passive"))
      (node (ref "X1") (pin "5") (pinfunction "1_5") (pintype "passive"))
    )
    (net (code "57") (name "Net-(U1-5C)") (class "Default")
      (node (ref "U1") (pin "14") (pinfunction "5C_14") (pintype "passive"))
      (node (ref "X1") (pin "6") (pinfunction "1_6") (pintype "passive"))
    )
    (net (code "58") (name "Net-(U1-6C)") (class "Default")
      (node (ref "U1") (pin "13") (pinfunction "6C_13") (pintype "passive"))
      (node (ref "X1") (pin "13") (pinfunction "1_13") (pintype "passive"))
    )
    (net (code "59") (name "Net-(U1-7C)") (class "Default")
      (node (ref "U1") (pin "12") (pinfunction "7C_12") (pintype "passive"))
      (node (ref "X1") (pin "14") (pinfunction "1_14") (pintype "passive"))
    )
    (net (code "60") (name "Net-(U1-8C)") (class "Default")
      (node (ref "U1") (pin "11") (pinfunction "8C_11") (pintype "passive"))
      (node (ref "X1") (pin "15") (pinfunction "1_15") (pintype "passive"))
    )
    (net (code "61") (name "Net-(U2-1C)") (class "Default")
      (node (ref "U2") (pin "18") (pinfunction "1C_18") (pintype "passive"))
      (node (ref "X1") (pin "12") (pinfunction "1_12") (pintype "passive"))
    )
    (net (code "62") (name "Net-(U2-2C)") (class "Default")
      (node (ref "U2") (pin "17") (pinfunction "2C_17") (pintype "passive"))
      (node (ref "X1") (pin "11") (pinfunction "1_11") (pintype "passive"))
    )
    (net (code "63") (name "Net-(U2-3C)") (class "Default")
      (node (ref "U2") (pin "16") (pinfunction "3C_16") (pintype "passive"))
      (node (ref "X1") (pin "10") (pinfunction "1_10") (pintype "passive"))
    )
    (net (code "64") (name "Net-(U2-4C)") (class "Default")
      (node (ref "U2") (pin "15") (pinfunction "4C_15") (pintype "passive"))
      (node (ref "X1") (pin "9") (pinfunction "1_9") (pintype "passive"))
    )
    (net (code "65") (name "Net-(U4-ADECAY)") (class "Default")
      (node (ref "R10") (pin "1") (pinfunction "1_1") (pintype "passive"))
      (node (ref "U4") (pin "24") (pinfunction "ADECAY_24") (pintype "input"))
    )
    (net (code "66") (name "Net-(U4-AISEN)") (class "Default")
      (node (ref "R16") (pin "1") (pinfunction "1_1") (pintype "passive"))
      (node (ref "U4") (pin "2") (pinfunction "AISEN_2") (pintype "bidirectional"))
    )
    (net (code "67") (name "Net-(U4-AOUT1)") (class "Default")
      (node (ref "J3") (pin "4") (pinfunction "4_4") (pintype "passive"))
      (node (ref "J4") (pin "4") (pinfunction "4_4") (pintype "passive"))
      (node (ref "U4") (pin "1") (pinfunction "AOUT1_1") (pintype "output"))
    )
    (net (code "68") (name "Net-(U4-AOUT2)") (class "Default")
      (node (ref "J3") (pin "3") (pinfunction "3_3") (pintype "passive"))
      (node (ref "J4") (pin "3") (pinfunction "3_3") (pintype "passive"))
      (node (ref "U4") (pin "3") (pinfunction "AOUT2_3") (pintype "output"))
    )
    (net (code "69") (name "Net-(U4-AVREF)") (class "Default")
      (node (ref "U4") (pin "19") (pinfunction "AVREF_19") (pintype "input"))
      (node (ref "U4") (pin "20") (pinfunction "BVREF_20") (pintype "input"))
      (node (ref "U4") (pin "21") (pinfunction "VREFO_21") (pintype "output"))
    )
    (net (code "70") (name "Net-(U4-BDECAY)") (class "Default")
      (node (ref "R17") (pin "1") (pinfunction "1_1") (pintype "passive"))
      (node (ref "U4") (pin "23") (pinfunction "BDECAY_23") (pintype "input"))
    )
    (net (code "71") (name "Net-(U4-BISEN)") (class "Default")
      (node (ref "R15") (pin "1") (pinfunction "1_1") (pintype "passive"))
      (node (ref "U4") (pin "5") (pinfunction "BISEN_5") (pintype "bidirectional"))
    )
    (net (code "72") (name "Net-(U4-BOUT1)") (class "Default")
      (node (ref "J3") (pin "1") (pinfunction "1_1") (pintype "passive"))
      (node (ref "J4") (pin "1") (pinfunction "1_1") (pintype "passive"))
      (node (ref "U4") (pin "6") (pinfunction "BOUT1_6") (pintype "output"))
    )
    (net (code "73") (name "Net-(U4-BOUT2)") (class "Default")
      (node (ref "J3") (pin "2") (pinfunction "2_2") (pintype "passive"))
      (node (ref "J4") (pin "2") (pinfunction "2_2") (pintype "passive"))
      (node (ref "U4") (pin "4") (pinfunction "BOUT2_4") (pintype "output"))
    )
    (net (code "74") (name "Net-(U4-M0{slash}APHASE)") (class "Default")
      (node (ref "J8") (pin "2") (pinfunction "2_2") (pintype "passive"))
      (node (ref "U4") (pin "10") (pinfunction "M0/APHASE_10") (pintype "input"))
    )
    (net (code "75") (name "Net-(U4-M1)") (class "Default")
      (node (ref "J8") (pin "1") (pinfunction "1_1") (pintype "passive"))
      (node (ref "U4") (pin "11") (pinfunction "M1_11") (pintype "input"))
    )
    (net (code "76") (name "Net-(U4-NFAULT)") (class "Default")
      (node (ref "R18") (pin "1") (pinfunction "1_1") (pintype "passive"))
      (node (ref "U4") (pin "13") (pinfunction "NFAULT_13") (pintype "output"))
    )
    (net (code "77") (name "Net-(U4-NSLEEP)") (class "Default")
      (node (ref "R19") (pin "1") (pinfunction "1_1") (pintype "passive"))
      (node (ref "U4") (pin "22") (pinfunction "NSLEEP_22") (pintype "input"))
    )
    (net (code "78") (name "Net-(U4-VCP)") (class "Default")
      (node (ref "0.01UF1") (pin "1") (pinfunction "1_1") (pintype "passive"))
      (node (ref "U4") (pin "14") (pinfunction "VCP_14") (pintype "output"))
    )
    (net (code "79") (name "Net-(U5-ADECAY)") (class "Default")
      (node (ref "R2") (pin "1") (pinfunction "1_1") (pintype "passive"))
      (node (ref "U5") (pin "24") (pinfunction "ADECAY_24") (pintype "input"))
    )
    (net (code "80") (name "Net-(U5-AISEN)") (class "Default")
      (node (ref "R4") (pin "1") (pinfunction "1_1") (pintype "passive"))
      (node (ref "U5") (pin "2") (pinfunction "AISEN_2") (pintype "bidirectional"))
    )
    (net (code "81") (name "Net-(U5-AOUT1)") (class "Default")
      (node (ref "J2") (pin "4") (pinfunction "4_4") (pintype "passive"))
      (node (ref "J5") (pin "4") (pinfunction "4_4") (pintype "passive"))
      (node (ref "U5") (pin "1") (pinfunction "AOUT1_1") (pintype "output"))
    )
    (net (code "82") (name "Net-(U5-AOUT2)") (class "Default")
      (node (ref "J2") (pin "3") (pinfunction "3_3") (pintype "passive"))
      (node (ref "J5") (pin "3") (pinfunction "3_3") (pintype "passive"))
      (node (ref "U5") (pin "3") (pinfunction "AOUT2_3") (pintype "output"))
    )
    (net (code "83") (name "Net-(U5-AVREF)") (class "Default")
      (node (ref "U5") (pin "19") (pinfunction "AVREF_19") (pintype "input"))
      (node (ref "U5") (pin "20") (pinfunction "BVREF_20") (pintype "input"))
      (node (ref "U5") (pin "21") (pinfunction "VREFO_21") (pintype "output"))
    )
    (net (code "84") (name "Net-(U5-BDECAY)") (class "Default")
      (node (ref "R5") (pin "1") (pinfunction "1_1") (pintype "passive"))
      (node (ref "U5") (pin "23") (pinfunction "BDECAY_23") (pintype "input"))
    )
    (net (code "85") (name "Net-(U5-BISEN)") (class "Default")
      (node (ref "R3") (pin "1") (pinfunction "1_1") (pintype "passive"))
      (node (ref "U5") (pin "5") (pinfunction "BISEN_5") (pintype "bidirectional"))
    )
    (net (code "86") (name "Net-(U5-BOUT1)") (class "Default")
      (node (ref "J2") (pin "2") (pinfunction "2_2") (pintype "passive"))
      (node (ref "J5") (pin "2") (pinfunction "2_2") (pintype "passive"))
      (node (ref "U5") (pin "6") (pinfunction "BOUT1_6") (pintype "output"))
    )
    (net (code "87") (name "Net-(U5-BOUT2)") (class "Default")
      (node (ref "J2") (pin "1") (pinfunction "1_1") (pintype "passive"))
      (node (ref "J5") (pin "1") (pinfunction "1_1") (pintype "passive"))
      (node (ref "U5") (pin "4") (pinfunction "BOUT2_4") (pintype "output"))
    )
    (net (code "88") (name "Net-(U5-M0{slash}APHASE)") (class "Default")
      (node (ref "J6") (pin "2") (pinfunction "2_2") (pintype "passive"))
      (node (ref "U5") (pin "10") (pinfunction "M0/APHASE_10") (pintype "input"))
    )
    (net (code "89") (name "Net-(U5-M1)") (class "Default")
      (node (ref "J6") (pin "1") (pinfunction "1_1") (pintype "passive"))
      (node (ref "U5") (pin "11") (pinfunction "M1_11") (pintype "input"))
    )
    (net (code "90") (name "Net-(U5-NFAULT)") (class "Default")
      (node (ref "R8") (pin "1") (pinfunction "1_1") (pintype "passive"))
      (node (ref "U5") (pin "13") (pinfunction "NFAULT_13") (pintype "output"))
    )
    (net (code "91") (name "Net-(U5-NSLEEP)") (class "Default")
      (node (ref "R9") (pin "1") (pinfunction "1_1") (pintype "passive"))
      (node (ref "U5") (pin "22") (pinfunction "NSLEEP_22") (pintype "input"))
    )
    (net (code "92") (name "Net-(U5-VCP)") (class "Default")
      (node (ref "0.01UF") (pin "1") (pinfunction "1_1") (pintype "passive"))
      (node (ref "U5") (pin "14") (pinfunction "VCP_14") (pintype "output"))
    )
    (net (code "93") (name "VCC") (class "Default")
      (node (ref "C21") (pin "1") (pinfunction "1_1") (pintype "passive"))
      (node (ref "C22") (pin "1") (pinfunction "1_1") (pintype "passive"))
      (node (ref "C23") (pin "1") (pinfunction "1_1") (pintype "passive"))
      (node (ref "C24") (pin "1") (pinfunction "1_1") (pintype "passive"))
      (node (ref "C5") (pin "1") (pinfunction "1_1") (pintype "passive"))
      (node (ref "S1") (pin "2") (pinfunction "P_2") (pintype "passive"))
      (node (ref "U3") (pin "1") (pinfunction "INPUT_1") (pintype "input"))
    )
    (net (code "94") (name "unconnected-(M1-IRQ-Pad8)") (class "Default")
      (node (ref "M1") (pin "8") (pinfunction "IRQ_8") (pintype "bidirectional"))
    )
    (net (code "95") (name "unconnected-(S1-S-Pad3)") (class "Default")
      (node (ref "S1") (pin "3") (pinfunction "S_3") (pintype "passive"))
    )
    (net (code "96") (name "unconnected-(U$2-GND2-PadGND1)") (class "Default")
      (node (ref "U$2") (pin "GND1") (pinfunction "GND2_GND1") (pintype "bidirectional"))
    )
    (net (code "97") (name "unconnected-(U$2-GND4-PadGND2)") (class "Default")
      (node (ref "U$2") (pin "GND2") (pinfunction "GND4_GND2") (pintype "bidirectional"))
    )
    (net (code "98") (name "unconnected-(U$2-PadA6)") (class "Default")
      (node (ref "U$2") (pin "A6") (pinfunction "A6_A6") (pintype "bidirectional"))
    )
    (net (code "99") (name "unconnected-(U$2-PadA7)") (class "Default")
      (node (ref "U$2") (pin "A7") (pinfunction "A7_A7") (pintype "bidirectional"))
    )
    (net (code "100") (name "unconnected-(U$2-PadD4)") (class "Default")
      (node (ref "U$2") (pin "D4") (pinfunction "D4_D4") (pintype "bidirectional"))
    )
    (net (code "101") (name "unconnected-(U$2-PadD6)") (class "Default")
      (node (ref "U$2") (pin "D6") (pinfunction "D6_D6") (pintype "bidirectional"))
    )
    (net (code "102") (name "unconnected-(U$2-PadDTR)") (class "Default")
      (node (ref "U$2") (pin "DTR") (pinfunction "DTR_DTR") (pintype "bidirectional"))
    )
    (net (code "103") (name "unconnected-(U$2-PadGND3)") (class "Default")
      (node (ref "U$2") (pin "GND3") (pinfunction "GND3_GND3") (pintype "bidirectional"))
    )
    (net (code "104") (name "unconnected-(U$2-PadRST)") (class "Default")
      (node (ref "U$2") (pin "RST") (pinfunction "RST_RST") (pintype "bidirectional"))
    )
    (net (code "105") (name "unconnected-(U$2-PadRX1-1)") (class "Default")
      (node (ref "U$2") (pin "RX1-1") (pinfunction "RX1-1_RX1-1") (pintype "bidirectional"))
    )
    (net (code "106") (name "unconnected-(U$2-PadTX0-1)") (class "Default")
      (node (ref "U$2") (pin "TX0-1") (pinfunction "TX0-1_TX0-1") (pintype "bidirectional"))
    )
    (net (code "107") (name "unconnected-(U$2-RST2-PadRST1)") (class "Default")
      (node (ref "U$2") (pin "RST1") (pinfunction "RST2_RST1") (pintype "bidirectional"))
    )
    (net (code "108") (name "unconnected-(U$2-VCC2-PadVCC1)") (class "Default")
      (node (ref "U$2") (pin "VCC1") (pinfunction "VCC2_VCC1") (pintype "bidirectional"))
    )
    (net (code "109") (name "unconnected-(U2-5C-Pad14)") (class "Default")
      (node (ref "U2") (pin "14") (pinfunction "5C_14") (pintype "passive"))
    )
    (net (code "110") (name "unconnected-(U2-6C-Pad13)") (class "Default")
      (node (ref "U2") (pin "13") (pinfunction "6C_13") (pintype "passive"))
    )
    (net (code "111") (name "unconnected-(U2-7C-Pad12)") (class "Default")
      (node (ref "U2") (pin "12") (pinfunction "7C_12") (pintype "passive"))
    )
    (net (code "112") (name "unconnected-(U2-8C-Pad11)") (class "Default")
      (node (ref "U2") (pin "11") (pinfunction "8C_11") (pintype "passive"))
    )
    (net (code "113") (name "unconnected-(U6-A0-Pad1)") (class "Default")
      (node (ref "U6") (pin "1") (pinfunction "A0_1") (pintype "input"))
    )
    (net (code "114") (name "unconnected-(U6-A1-Pad2)") (class "Default")
      (node (ref "U6") (pin "2") (pinfunction "A1_2") (pintype "input"))
    )
    (net (code "115") (name "unconnected-(U6-A2-Pad3)") (class "Default")
      (node (ref "U6") (pin "3") (pinfunction "A2_3") (pintype "input"))
    )
    (net (code "116") (name "unconnected-(X1-Pad1)") (class "Default")
      (node (ref "X1") (pin "1") (pinfunction "1_1") (pintype "passive"))
    )
    (net (code "117") (name "unconnected-(X1I-1-Pad2)") (class "Default")
      (node (ref "X1") (pin "2") (pinfunction "1_2") (pintype "passive"))
    )
  )
)
